# Cap_Sensor_8x8.net
KiCad netlist of a schematic drawn in Altium Designer
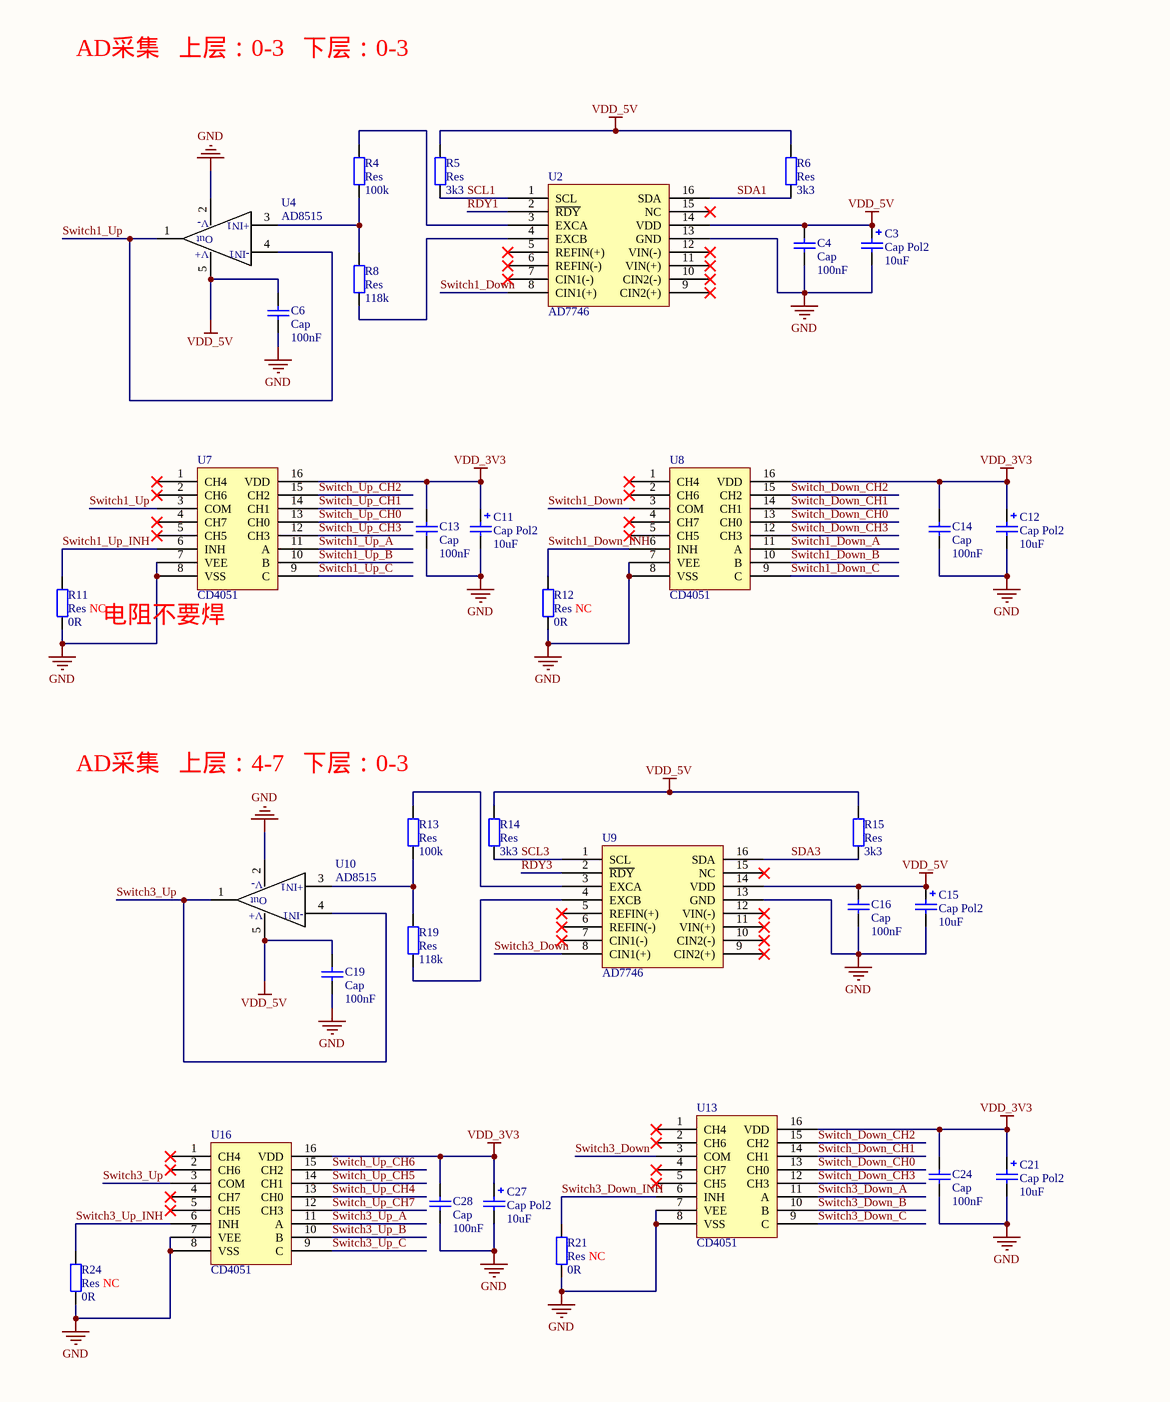
[diagram p0: Cap_Sensor_8x8.SchDoc, left]
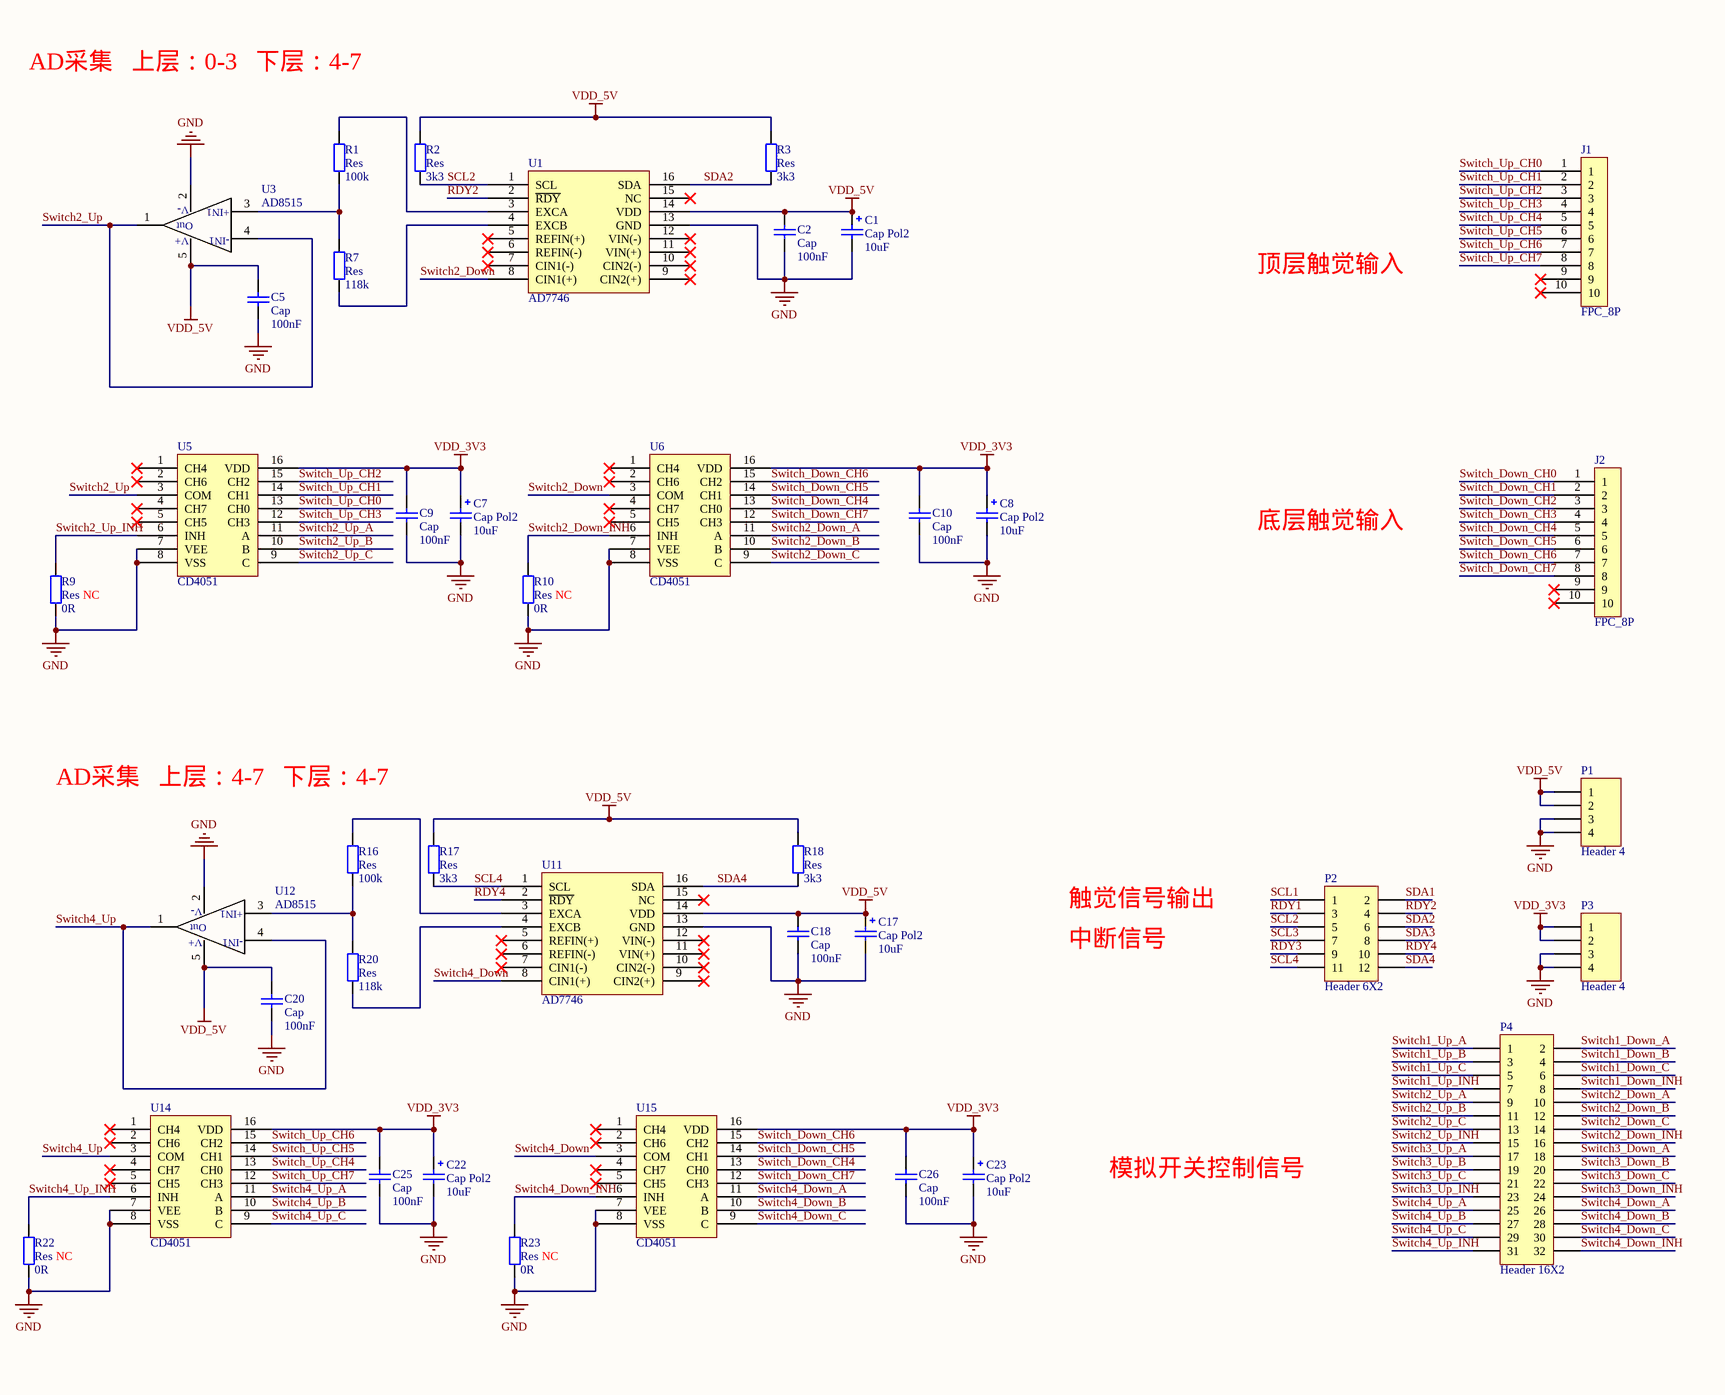
[diagram p1: Cap_Sensor_8x8.SchDoc, right]

(export (version "E")
  (design (tool "Eeschema 10.0.6"))
  (components
    (comp (ref "C1")
      (value "Cap Pol2")
      (footprint "Cap-TA")
      (description "Polarized Capacitor (Axial)")
      (fields (field (name "ALTIUM_VALUE") "10uF") (field (name "PUBLISHER") "Altium Limited"))
      (libsource (lib "YD-LibrarySCH") (part "Cap Pol2"))
    )
    (comp (ref "C2")
      (value "Cap")
      (footprint "0805C")
      (description "Capacitor")
      (fields (field (name "ALTIUM_VALUE") "100nF") (field (name "PUBLISHER") "Altium Limited"))
      (libsource (lib "YD-LibrarySCH") (part "Cap"))
    )
    (comp (ref "C3")
      (value "Cap Pol2")
      (footprint "Cap-TA")
      (description "Polarized Capacitor (Axial)")
      (fields (field (name "ALTIUM_VALUE") "10uF") (field (name "PUBLISHER") "Altium Limited"))
      (libsource (lib "YD-LibrarySCH") (part "Cap Pol2"))
    )
    (comp (ref "C4")
      (value "Cap")
      (footprint "0805C")
      (description "Capacitor")
      (fields (field (name "ALTIUM_VALUE") "100nF") (field (name "PUBLISHER") "Altium Limited"))
      (libsource (lib "YD-LibrarySCH") (part "Cap"))
    )
    (comp (ref "C5")
      (value "Cap")
      (footprint "0805C")
      (description "Capacitor")
      (fields (field (name "ALTIUM_VALUE") "100nF") (field (name "PUBLISHER") "Altium Limited"))
      (libsource (lib "YD-LibrarySCH") (part "Cap"))
    )
    (comp (ref "C6")
      (value "Cap")
      (footprint "0805C")
      (description "Capacitor")
      (fields (field (name "ALTIUM_VALUE") "100nF") (field (name "PUBLISHER") "Altium Limited"))
      (libsource (lib "YD-LibrarySCH") (part "Cap"))
    )
    (comp (ref "C7")
      (value "Cap Pol2")
      (footprint "Cap-TA")
      (description "Polarized Capacitor (Axial)")
      (fields (field (name "ALTIUM_VALUE") "10uF") (field (name "PUBLISHER") "Altium Limited"))
      (libsource (lib "YD-LibrarySCH") (part "Cap Pol2"))
    )
    (comp (ref "C8")
      (value "Cap Pol2")
      (footprint "Cap-TA")
      (description "Polarized Capacitor (Axial)")
      (fields (field (name "ALTIUM_VALUE") "10uF") (field (name "PUBLISHER") "Altium Limited"))
      (libsource (lib "YD-LibrarySCH") (part "Cap Pol2"))
    )
    (comp (ref "C9")
      (value "Cap")
      (footprint "0805C")
      (description "Capacitor")
      (fields (field (name "ALTIUM_VALUE") "100nF") (field (name "PUBLISHER") "Altium Limited"))
      (libsource (lib "YD-LibrarySCH") (part "Cap"))
    )
    (comp (ref "C10")
      (value "Cap")
      (footprint "0805C")
      (description "Capacitor")
      (fields (field (name "ALTIUM_VALUE") "100nF") (field (name "PUBLISHER") "Altium Limited"))
      (libsource (lib "YD-LibrarySCH") (part "Cap"))
    )
    (comp (ref "C11")
      (value "Cap Pol2")
      (footprint "Cap-TA")
      (description "Polarized Capacitor (Axial)")
      (fields (field (name "ALTIUM_VALUE") "10uF") (field (name "PUBLISHER") "Altium Limited"))
      (libsource (lib "YD-LibrarySCH") (part "Cap Pol2"))
    )
    (comp (ref "C12")
      (value "Cap Pol2")
      (footprint "Cap-TA")
      (description "Polarized Capacitor (Axial)")
      (fields (field (name "ALTIUM_VALUE") "10uF") (field (name "PUBLISHER") "Altium Limited"))
      (libsource (lib "YD-LibrarySCH") (part "Cap Pol2"))
    )
    (comp (ref "C13")
      (value "Cap")
      (footprint "0805C")
      (description "Capacitor")
      (fields (field (name "ALTIUM_VALUE") "100nF") (field (name "PUBLISHER") "Altium Limited"))
      (libsource (lib "YD-LibrarySCH") (part "Cap"))
    )
    (comp (ref "C14")
      (value "Cap")
      (footprint "0805C")
      (description "Capacitor")
      (fields (field (name "ALTIUM_VALUE") "100nF") (field (name "PUBLISHER") "Altium Limited"))
      (libsource (lib "YD-LibrarySCH") (part "Cap"))
    )
    (comp (ref "C15")
      (value "Cap Pol2")
      (footprint "Cap-TA")
      (description "Polarized Capacitor (Axial)")
      (fields (field (name "ALTIUM_VALUE") "10uF") (field (name "PUBLISHER") "Altium Limited"))
      (libsource (lib "YD-LibrarySCH") (part "Cap Pol2"))
    )
    (comp (ref "C16")
      (value "Cap")
      (footprint "0805C")
      (description "Capacitor")
      (fields (field (name "ALTIUM_VALUE") "100nF") (field (name "PUBLISHER") "Altium Limited"))
      (libsource (lib "YD-LibrarySCH") (part "Cap"))
    )
    (comp (ref "C17")
      (value "Cap Pol2")
      (footprint "Cap-TA")
      (description "Polarized Capacitor (Axial)")
      (fields (field (name "ALTIUM_VALUE") "10uF") (field (name "PUBLISHER") "Altium Limited"))
      (libsource (lib "YD-LibrarySCH") (part "Cap Pol2"))
    )
    (comp (ref "C18")
      (value "Cap")
      (footprint "0805C")
      (description "Capacitor")
      (fields (field (name "ALTIUM_VALUE") "100nF") (field (name "PUBLISHER") "Altium Limited"))
      (libsource (lib "YD-LibrarySCH") (part "Cap"))
    )
    (comp (ref "C19")
      (value "Cap")
      (footprint "0805C")
      (description "Capacitor")
      (fields (field (name "ALTIUM_VALUE") "100nF") (field (name "PUBLISHER") "Altium Limited"))
      (libsource (lib "YD-LibrarySCH") (part "Cap"))
    )
    (comp (ref "C20")
      (value "Cap")
      (footprint "0805C")
      (description "Capacitor")
      (fields (field (name "ALTIUM_VALUE") "100nF") (field (name "PUBLISHER") "Altium Limited"))
      (libsource (lib "YD-LibrarySCH") (part "Cap"))
    )
    (comp (ref "C21")
      (value "Cap Pol2")
      (footprint "Cap-TA")
      (description "Polarized Capacitor (Axial)")
      (fields (field (name "ALTIUM_VALUE") "10uF") (field (name "PUBLISHER") "Altium Limited"))
      (libsource (lib "YD-LibrarySCH") (part "Cap Pol2"))
    )
    (comp (ref "C22")
      (value "Cap Pol2")
      (footprint "Cap-TA")
      (description "Polarized Capacitor (Axial)")
      (fields (field (name "ALTIUM_VALUE") "10uF") (field (name "PUBLISHER") "Altium Limited"))
      (libsource (lib "YD-LibrarySCH") (part "Cap Pol2"))
    )
    (comp (ref "C23")
      (value "Cap Pol2")
      (footprint "Cap-TA")
      (description "Polarized Capacitor (Axial)")
      (fields (field (name "ALTIUM_VALUE") "10uF") (field (name "PUBLISHER") "Altium Limited"))
      (libsource (lib "YD-LibrarySCH") (part "Cap Pol2"))
    )
    (comp (ref "C24")
      (value "Cap")
      (footprint "0805C")
      (description "Capacitor")
      (fields (field (name "ALTIUM_VALUE") "100nF") (field (name "PUBLISHER") "Altium Limited"))
      (libsource (lib "YD-LibrarySCH") (part "Cap"))
    )
    (comp (ref "C25")
      (value "Cap")
      (footprint "0805C")
      (description "Capacitor")
      (fields (field (name "ALTIUM_VALUE") "100nF") (field (name "PUBLISHER") "Altium Limited"))
      (libsource (lib "YD-LibrarySCH") (part "Cap"))
    )
    (comp (ref "C26")
      (value "Cap")
      (footprint "0805C")
      (description "Capacitor")
      (fields (field (name "ALTIUM_VALUE") "100nF") (field (name "PUBLISHER") "Altium Limited"))
      (libsource (lib "YD-LibrarySCH") (part "Cap"))
    )
    (comp (ref "C27")
      (value "Cap Pol2")
      (footprint "Cap-TA")
      (description "Polarized Capacitor (Axial)")
      (fields (field (name "ALTIUM_VALUE") "10uF") (field (name "PUBLISHER") "Altium Limited"))
      (libsource (lib "YD-LibrarySCH") (part "Cap Pol2"))
    )
    (comp (ref "C28")
      (value "Cap")
      (footprint "0805C")
      (description "Capacitor")
      (fields (field (name "ALTIUM_VALUE") "100nF") (field (name "PUBLISHER") "Altium Limited"))
      (libsource (lib "YD-LibrarySCH") (part "Cap"))
    )
    (comp (ref "J1")
      (value "FPC_8P")
      (footprint "FPC8-0.5")
      (libsource (lib "YD-LibrarySCH") (part "FPC_8P"))
    )
    (comp (ref "J2")
      (value "FPC_8P")
      (footprint "FPC8-0.5")
      (libsource (lib "YD-LibrarySCH") (part "FPC_8P"))
    )
    (comp (ref "P1")
      (value "Header 4")
      (footprint "HDR1X4")
      (description "Header, 4-Pin")
      (fields (field (name "PUBLISHER") "Altium Limited"))
      (libsource (lib "YD-LibrarySCH") (part "Header 4"))
    )
    (comp (ref "P2")
      (value "Header 6X2")
      (footprint "HDR2X6")
      (description "Header, 6-Pin, Dual row")
      (fields (field (name "PUBLISHER") "Altium Limited"))
      (libsource (lib "YD-LibrarySCH") (part "Header 6X2"))
    )
    (comp (ref "P3")
      (value "Header 4")
      (footprint "HDR1X4")
      (description "Header, 4-Pin")
      (fields (field (name "PUBLISHER") "Altium Limited"))
      (libsource (lib "YD-LibrarySCH") (part "Header 4"))
    )
    (comp (ref "P4")
      (value "Header 16X2")
      (footprint "HDR2X16")
      (description "Header, 16-Pin, Dual row")
      (fields (field (name "PUBLISHER") "Altium Limited"))
      (libsource (lib "YD-LibrarySCH") (part "Header 16X2"))
    )
    (comp (ref "R1")
      (value "Res")
      (footprint "0805R")
      (description "Resistor")
      (fields (field (name "ALTIUM_VALUE") "100k") (field (name "PUBLISHER") "Altium Limited"))
      (libsource (lib "") (part "Res_1"))
    )
    (comp (ref "R2")
      (value "Res")
      (footprint "0805R")
      (description "Resistor")
      (fields (field (name "ALTIUM_VALUE") "3k3") (field (name "PUBLISHER") "Altium Limited"))
      (libsource (lib "YD-LibrarySCH") (part "Res"))
    )
    (comp (ref "R3")
      (value "Res")
      (footprint "0805R")
      (description "Resistor")
      (fields (field (name "ALTIUM_VALUE") "3k3") (field (name "PUBLISHER") "Altium Limited"))
      (libsource (lib "YD-LibrarySCH") (part "Res"))
    )
    (comp (ref "R4")
      (value "Res")
      (footprint "0805R")
      (description "Resistor")
      (fields (field (name "ALTIUM_VALUE") "100k") (field (name "PUBLISHER") "Altium Limited"))
      (libsource (lib "") (part "Res_1"))
    )
    (comp (ref "R5")
      (value "Res")
      (footprint "0805R")
      (description "Resistor")
      (fields (field (name "ALTIUM_VALUE") "3k3") (field (name "PUBLISHER") "Altium Limited"))
      (libsource (lib "YD-LibrarySCH") (part "Res"))
    )
    (comp (ref "R6")
      (value "Res")
      (footprint "0805R")
      (description "Resistor")
      (fields (field (name "ALTIUM_VALUE") "3k3") (field (name "PUBLISHER") "Altium Limited"))
      (libsource (lib "YD-LibrarySCH") (part "Res"))
    )
    (comp (ref "R7")
      (value "Res")
      (footprint "0805R")
      (description "Resistor")
      (fields (field (name "ALTIUM_VALUE") "118k") (field (name "PUBLISHER") "Altium Limited"))
      (libsource (lib "") (part "Res_1"))
    )
    (comp (ref "R8")
      (value "Res")
      (footprint "0805R")
      (description "Resistor")
      (fields (field (name "ALTIUM_VALUE") "118k") (field (name "PUBLISHER") "Altium Limited"))
      (libsource (lib "") (part "Res_1"))
    )
    (comp (ref "R9")
      (value "Res")
      (footprint "0805R")
      (description "Resistor")
      (fields (field (name "ALTIUM_VALUE") "0R") (field (name "PUBLISHER") "Altium Limited"))
      (libsource (lib "YD-LibrarySCH") (part "Res"))
    )
    (comp (ref "R10")
      (value "Res")
      (footprint "0603R")
      (description "Resistor")
      (fields (field (name "ALTIUM_VALUE") "0R") (field (name "PUBLISHER") "Altium Limited"))
      (libsource (lib "YD-LibrarySCH") (part "Res"))
    )
    (comp (ref "R11")
      (value "Res")
      (footprint "0805R")
      (description "Resistor")
      (fields (field (name "ALTIUM_VALUE") "0R") (field (name "PUBLISHER") "Altium Limited"))
      (libsource (lib "YD-LibrarySCH") (part "Res"))
    )
    (comp (ref "R12")
      (value "Res")
      (footprint "0603R")
      (description "Resistor")
      (fields (field (name "ALTIUM_VALUE") "0R") (field (name "PUBLISHER") "Altium Limited"))
      (libsource (lib "YD-LibrarySCH") (part "Res"))
    )
    (comp (ref "R13")
      (value "Res")
      (footprint "0805R")
      (description "Resistor")
      (fields (field (name "ALTIUM_VALUE") "100k") (field (name "PUBLISHER") "Altium Limited"))
      (libsource (lib "") (part "Res_1"))
    )
    (comp (ref "R14")
      (value "Res")
      (footprint "0805R")
      (description "Resistor")
      (fields (field (name "ALTIUM_VALUE") "3k3") (field (name "PUBLISHER") "Altium Limited"))
      (libsource (lib "YD-LibrarySCH") (part "Res"))
    )
    (comp (ref "R15")
      (value "Res")
      (footprint "0805R")
      (description "Resistor")
      (fields (field (name "ALTIUM_VALUE") "3k3") (field (name "PUBLISHER") "Altium Limited"))
      (libsource (lib "YD-LibrarySCH") (part "Res"))
    )
    (comp (ref "R16")
      (value "Res")
      (footprint "0805R")
      (description "Resistor")
      (fields (field (name "ALTIUM_VALUE") "100k") (field (name "PUBLISHER") "Altium Limited"))
      (libsource (lib "") (part "Res_1"))
    )
    (comp (ref "R17")
      (value "Res")
      (footprint "0805R")
      (description "Resistor")
      (fields (field (name "ALTIUM_VALUE") "3k3") (field (name "PUBLISHER") "Altium Limited"))
      (libsource (lib "YD-LibrarySCH") (part "Res"))
    )
    (comp (ref "R18")
      (value "Res")
      (footprint "0805R")
      (description "Resistor")
      (fields (field (name "ALTIUM_VALUE") "3k3") (field (name "PUBLISHER") "Altium Limited"))
      (libsource (lib "YD-LibrarySCH") (part "Res"))
    )
    (comp (ref "R19")
      (value "Res")
      (footprint "0805R")
      (description "Resistor")
      (fields (field (name "ALTIUM_VALUE") "118k") (field (name "PUBLISHER") "Altium Limited"))
      (libsource (lib "") (part "Res_1"))
    )
    (comp (ref "R20")
      (value "Res")
      (footprint "0805R")
      (description "Resistor")
      (fields (field (name "ALTIUM_VALUE") "118k") (field (name "PUBLISHER") "Altium Limited"))
      (libsource (lib "") (part "Res_1"))
    )
    (comp (ref "R21")
      (value "Res")
      (footprint "0603R")
      (description "Resistor")
      (fields (field (name "ALTIUM_VALUE") "0R") (field (name "PUBLISHER") "Altium Limited"))
      (libsource (lib "YD-LibrarySCH") (part "Res"))
    )
    (comp (ref "R22")
      (value "Res")
      (footprint "0805R")
      (description "Resistor")
      (fields (field (name "ALTIUM_VALUE") "0R") (field (name "PUBLISHER") "Altium Limited"))
      (libsource (lib "YD-LibrarySCH") (part "Res"))
    )
    (comp (ref "R23")
      (value "Res")
      (footprint "0603R")
      (description "Resistor")
      (fields (field (name "ALTIUM_VALUE") "0R") (field (name "PUBLISHER") "Altium Limited"))
      (libsource (lib "YD-LibrarySCH") (part "Res"))
    )
    (comp (ref "R24")
      (value "Res")
      (footprint "0805R")
      (description "Resistor")
      (fields (field (name "ALTIUM_VALUE") "0R") (field (name "PUBLISHER") "Altium Limited"))
      (libsource (lib "YD-LibrarySCH") (part "Res"))
    )
    (comp (ref "U1") (value "AD7746") (footprint "TSSOP16") (libsource (lib "YD-LibrarySCH") (part "AD7746")))
    (comp (ref "U2") (value "AD7746") (footprint "TSSOP16") (libsource (lib "YD-LibrarySCH") (part "AD7746")))
    (comp (ref "U3") (value "AD8515") (footprint "sot23-5") (libsource (lib "YD-LibrarySCH") (part "AD8515")))
    (comp (ref "U4") (value "AD8515") (footprint "sot23-5") (libsource (lib "YD-LibrarySCH") (part "AD8515")))
    (comp (ref "U5") (value "CD4051") (footprint "SO16") (libsource (lib "YD-LibrarySCH") (part "CD4051")))
    (comp (ref "U6") (value "CD4051") (footprint "SO16") (libsource (lib "YD-LibrarySCH") (part "CD4051")))
    (comp (ref "U7") (value "CD4051") (footprint "SO16") (libsource (lib "YD-LibrarySCH") (part "CD4051")))
    (comp (ref "U8") (value "CD4051") (footprint "SO16") (libsource (lib "YD-LibrarySCH") (part "CD4051")))
    (comp (ref "U9") (value "AD7746") (footprint "TSSOP16") (libsource (lib "YD-LibrarySCH") (part "AD7746")))
    (comp (ref "U10")
      (value "AD8515")
      (footprint "sot23-5")
      (libsource (lib "YD-LibrarySCH") (part "AD8515"))
    )
    (comp (ref "U11")
      (value "AD7746")
      (footprint "TSSOP16")
      (libsource (lib "YD-LibrarySCH") (part "AD7746"))
    )
    (comp (ref "U12")
      (value "AD8515")
      (footprint "sot23-5")
      (libsource (lib "YD-LibrarySCH") (part "AD8515"))
    )
    (comp (ref "U13") (value "CD4051") (footprint "SO16") (libsource (lib "YD-LibrarySCH") (part "CD4051")))
    (comp (ref "U14") (value "CD4051") (footprint "SO16") (libsource (lib "YD-LibrarySCH") (part "CD4051")))
    (comp (ref "U15") (value "CD4051") (footprint "SO16") (libsource (lib "YD-LibrarySCH") (part "CD4051")))
    (comp (ref "U16") (value "CD4051") (footprint "SO16") (libsource (lib "YD-LibrarySCH") (part "CD4051")))
  )
  (nets
    (net (code "1") (name "/RDY1") (class "Default")
      (node (ref "P2") (pin "3") (pinfunction "3_3") (pintype "passive"))
      (node (ref "U2") (pin "2") (pinfunction "~{RDY}_2") (pintype "passive"))
    )
    (net (code "2") (name "/RDY2") (class "Default")
      (node (ref "P2") (pin "4") (pinfunction "4_4") (pintype "passive"))
      (node (ref "U1") (pin "2") (pinfunction "~{RDY}_2") (pintype "passive"))
    )
    (net (code "3") (name "/RDY3") (class "Default")
      (node (ref "P2") (pin "9") (pinfunction "9_9") (pintype "passive"))
      (node (ref "U9") (pin "2") (pinfunction "~{RDY}_2") (pintype "passive"))
    )
    (net (code "4") (name "/RDY4") (class "Default")
      (node (ref "P2") (pin "10") (pinfunction "10_10") (pintype "passive"))
      (node (ref "U11") (pin "2") (pinfunction "~{RDY}_2") (pintype "passive"))
    )
    (net (code "5") (name "/SCL1") (class "Default")
      (node (ref "P2") (pin "1") (pinfunction "1_1") (pintype "passive"))
      (node (ref "R5") (pin "1") (pinfunction "1_1") (pintype "passive"))
      (node (ref "U2") (pin "1") (pinfunction "SCL_1") (pintype "passive"))
    )
    (net (code "6") (name "/SCL2") (class "Default")
      (node (ref "P2") (pin "5") (pinfunction "5_5") (pintype "passive"))
      (node (ref "R2") (pin "1") (pinfunction "1_1") (pintype "passive"))
      (node (ref "U1") (pin "1") (pinfunction "SCL_1") (pintype "passive"))
    )
    (net (code "7") (name "/SCL3") (class "Default")
      (node (ref "P2") (pin "7") (pinfunction "7_7") (pintype "passive"))
      (node (ref "R14") (pin "1") (pinfunction "1_1") (pintype "passive"))
      (node (ref "U9") (pin "1") (pinfunction "SCL_1") (pintype "passive"))
    )
    (net (code "8") (name "/SCL4") (class "Default")
      (node (ref "P2") (pin "11") (pinfunction "11_11") (pintype "passive"))
      (node (ref "R17") (pin "1") (pinfunction "1_1") (pintype "passive"))
      (node (ref "U11") (pin "1") (pinfunction "SCL_1") (pintype "passive"))
    )
    (net (code "9") (name "/SDA1") (class "Default")
      (node (ref "P2") (pin "2") (pinfunction "2_2") (pintype "passive"))
      (node (ref "R6") (pin "1") (pinfunction "1_1") (pintype "passive"))
      (node (ref "U2") (pin "16") (pinfunction "SDA_16") (pintype "passive"))
    )
    (net (code "10") (name "/SDA2") (class "Default")
      (node (ref "P2") (pin "6") (pinfunction "6_6") (pintype "passive"))
      (node (ref "R3") (pin "1") (pinfunction "1_1") (pintype "passive"))
      (node (ref "U1") (pin "16") (pinfunction "SDA_16") (pintype "passive"))
    )
    (net (code "11") (name "/SDA3") (class "Default")
      (node (ref "P2") (pin "8") (pinfunction "8_8") (pintype "passive"))
      (node (ref "R15") (pin "1") (pinfunction "1_1") (pintype "passive"))
      (node (ref "U9") (pin "16") (pinfunction "SDA_16") (pintype "passive"))
    )
    (net (code "12") (name "/SDA4") (class "Default")
      (node (ref "P2") (pin "12") (pinfunction "12_12") (pintype "passive"))
      (node (ref "R18") (pin "1") (pinfunction "1_1") (pintype "passive"))
      (node (ref "U11") (pin "16") (pinfunction "SDA_16") (pintype "passive"))
    )
    (net (code "13") (name "/Switch1_Down") (class "Default")
      (node (ref "U2") (pin "8") (pinfunction "CIN1(+)_8") (pintype "passive"))
      (node (ref "U8") (pin "3") (pinfunction "COM_3") (pintype "passive"))
    )
    (net (code "14") (name "/Switch1_Down_A") (class "Default")
      (node (ref "P4") (pin "2") (pinfunction "2_2") (pintype "passive"))
      (node (ref "U8") (pin "11") (pinfunction "A_11") (pintype "passive"))
    )
    (net (code "15") (name "/Switch1_Down_B") (class "Default")
      (node (ref "P4") (pin "4") (pinfunction "4_4") (pintype "passive"))
      (node (ref "U8") (pin "10") (pinfunction "B_10") (pintype "passive"))
    )
    (net (code "16") (name "/Switch1_Down_C") (class "Default")
      (node (ref "P4") (pin "6") (pinfunction "6_6") (pintype "passive"))
      (node (ref "U8") (pin "9") (pinfunction "C_9") (pintype "passive"))
    )
    (net (code "17") (name "/Switch1_Down_INH") (class "Default")
      (node (ref "P4") (pin "8") (pinfunction "8_8") (pintype "passive"))
      (node (ref "R12") (pin "2") (pinfunction "2_2") (pintype "passive"))
      (node (ref "U8") (pin "6") (pinfunction "INH_6") (pintype "passive"))
    )
    (net (code "18") (name "/Switch1_Up") (class "Default")
      (node (ref "U4") (pin "1") (pinfunction "Out1_1") (pintype "passive"))
      (node (ref "U4") (pin "4") (pinfunction "-IN_4") (pintype "passive"))
      (node (ref "U7") (pin "3") (pinfunction "COM_3") (pintype "passive"))
    )
    (net (code "19") (name "/Switch1_Up_A") (class "Default")
      (node (ref "P4") (pin "1") (pinfunction "1_1") (pintype "passive"))
      (node (ref "U7") (pin "11") (pinfunction "A_11") (pintype "passive"))
    )
    (net (code "20") (name "/Switch1_Up_B") (class "Default")
      (node (ref "P4") (pin "3") (pinfunction "3_3") (pintype "passive"))
      (node (ref "U7") (pin "10") (pinfunction "B_10") (pintype "passive"))
    )
    (net (code "21") (name "/Switch1_Up_C") (class "Default")
      (node (ref "P4") (pin "5") (pinfunction "5_5") (pintype "passive"))
      (node (ref "U7") (pin "9") (pinfunction "C_9") (pintype "passive"))
    )
    (net (code "22") (name "/Switch1_Up_INH") (class "Default")
      (node (ref "P4") (pin "7") (pinfunction "7_7") (pintype "passive"))
      (node (ref "R11") (pin "2") (pinfunction "2_2") (pintype "passive"))
      (node (ref "U7") (pin "6") (pinfunction "INH_6") (pintype "passive"))
    )
    (net (code "23") (name "/Switch2_Down") (class "Default")
      (node (ref "U1") (pin "8") (pinfunction "CIN1(+)_8") (pintype "passive"))
      (node (ref "U6") (pin "3") (pinfunction "COM_3") (pintype "passive"))
    )
    (net (code "24") (name "/Switch2_Down_A") (class "Default")
      (node (ref "P4") (pin "10") (pinfunction "10_10") (pintype "passive"))
      (node (ref "U6") (pin "11") (pinfunction "A_11") (pintype "passive"))
    )
    (net (code "25") (name "/Switch2_Down_B") (class "Default")
      (node (ref "P4") (pin "12") (pinfunction "12_12") (pintype "passive"))
      (node (ref "U6") (pin "10") (pinfunction "B_10") (pintype "passive"))
    )
    (net (code "26") (name "/Switch2_Down_C") (class "Default")
      (node (ref "P4") (pin "14") (pinfunction "14_14") (pintype "passive"))
      (node (ref "U6") (pin "9") (pinfunction "C_9") (pintype "passive"))
    )
    (net (code "27") (name "/Switch2_Down_INH") (class "Default")
      (node (ref "P4") (pin "16") (pinfunction "16_16") (pintype "passive"))
      (node (ref "R10") (pin "2") (pinfunction "2_2") (pintype "passive"))
      (node (ref "U6") (pin "6") (pinfunction "INH_6") (pintype "passive"))
    )
    (net (code "28") (name "/Switch2_Up") (class "Default")
      (node (ref "U3") (pin "1") (pinfunction "Out1_1") (pintype "passive"))
      (node (ref "U3") (pin "4") (pinfunction "-IN_4") (pintype "passive"))
      (node (ref "U5") (pin "3") (pinfunction "COM_3") (pintype "passive"))
    )
    (net (code "29") (name "/Switch2_Up_A") (class "Default")
      (node (ref "P4") (pin "9") (pinfunction "9_9") (pintype "passive"))
      (node (ref "U5") (pin "11") (pinfunction "A_11") (pintype "passive"))
    )
    (net (code "30") (name "/Switch2_Up_B") (class "Default")
      (node (ref "P4") (pin "11") (pinfunction "11_11") (pintype "passive"))
      (node (ref "U5") (pin "10") (pinfunction "B_10") (pintype "passive"))
    )
    (net (code "31") (name "/Switch2_Up_C") (class "Default")
      (node (ref "P4") (pin "13") (pinfunction "13_13") (pintype "passive"))
      (node (ref "U5") (pin "9") (pinfunction "C_9") (pintype "passive"))
    )
    (net (code "32") (name "/Switch2_Up_INH") (class "Default")
      (node (ref "P4") (pin "15") (pinfunction "15_15") (pintype "passive"))
      (node (ref "R9") (pin "2") (pinfunction "2_2") (pintype "passive"))
      (node (ref "U5") (pin "6") (pinfunction "INH_6") (pintype "passive"))
    )
    (net (code "33") (name "/Switch3_Down") (class "Default")
      (node (ref "U13") (pin "3") (pinfunction "COM_3") (pintype "passive"))
      (node (ref "U9") (pin "8") (pinfunction "CIN1(+)_8") (pintype "passive"))
    )
    (net (code "34") (name "/Switch3_Down_A") (class "Default")
      (node (ref "P4") (pin "18") (pinfunction "18_18") (pintype "passive"))
      (node (ref "U13") (pin "11") (pinfunction "A_11") (pintype "passive"))
    )
    (net (code "35") (name "/Switch3_Down_B") (class "Default")
      (node (ref "P4") (pin "20") (pinfunction "20_20") (pintype "passive"))
      (node (ref "U13") (pin "10") (pinfunction "B_10") (pintype "passive"))
    )
    (net (code "36") (name "/Switch3_Down_C") (class "Default")
      (node (ref "P4") (pin "22") (pinfunction "22_22") (pintype "passive"))
      (node (ref "U13") (pin "9") (pinfunction "C_9") (pintype "passive"))
    )
    (net (code "37") (name "/Switch3_Down_INH") (class "Default")
      (node (ref "P4") (pin "24") (pinfunction "24_24") (pintype "passive"))
      (node (ref "R21") (pin "2") (pinfunction "2_2") (pintype "passive"))
      (node (ref "U13") (pin "6") (pinfunction "INH_6") (pintype "passive"))
    )
    (net (code "38") (name "/Switch3_Up") (class "Default")
      (node (ref "U10") (pin "1") (pinfunction "Out1_1") (pintype "passive"))
      (node (ref "U10") (pin "4") (pinfunction "-IN_4") (pintype "passive"))
      (node (ref "U16") (pin "3") (pinfunction "COM_3") (pintype "passive"))
    )
    (net (code "39") (name "/Switch3_Up_A") (class "Default")
      (node (ref "P4") (pin "17") (pinfunction "17_17") (pintype "passive"))
      (node (ref "U16") (pin "11") (pinfunction "A_11") (pintype "passive"))
    )
    (net (code "40") (name "/Switch3_Up_B") (class "Default")
      (node (ref "P4") (pin "19") (pinfunction "19_19") (pintype "passive"))
      (node (ref "U16") (pin "10") (pinfunction "B_10") (pintype "passive"))
    )
    (net (code "41") (name "/Switch3_Up_C") (class "Default")
      (node (ref "P4") (pin "21") (pinfunction "21_21") (pintype "passive"))
      (node (ref "U16") (pin "9") (pinfunction "C_9") (pintype "passive"))
    )
    (net (code "42") (name "/Switch3_Up_INH") (class "Default")
      (node (ref "P4") (pin "23") (pinfunction "23_23") (pintype "passive"))
      (node (ref "R24") (pin "2") (pinfunction "2_2") (pintype "passive"))
      (node (ref "U16") (pin "6") (pinfunction "INH_6") (pintype "passive"))
    )
    (net (code "43") (name "/Switch4_Down") (class "Default")
      (node (ref "U11") (pin "8") (pinfunction "CIN1(+)_8") (pintype "passive"))
      (node (ref "U15") (pin "3") (pinfunction "COM_3") (pintype "passive"))
    )
    (net (code "44") (name "/Switch4_Down_A") (class "Default")
      (node (ref "P4") (pin "26") (pinfunction "26_26") (pintype "passive"))
      (node (ref "U15") (pin "11") (pinfunction "A_11") (pintype "passive"))
    )
    (net (code "45") (name "/Switch4_Down_B") (class "Default")
      (node (ref "P4") (pin "28") (pinfunction "28_28") (pintype "passive"))
      (node (ref "U15") (pin "10") (pinfunction "B_10") (pintype "passive"))
    )
    (net (code "46") (name "/Switch4_Down_C") (class "Default")
      (node (ref "P4") (pin "30") (pinfunction "30_30") (pintype "passive"))
      (node (ref "U15") (pin "9") (pinfunction "C_9") (pintype "passive"))
    )
    (net (code "47") (name "/Switch4_Down_INH") (class "Default")
      (node (ref "P4") (pin "32") (pinfunction "32_32") (pintype "passive"))
      (node (ref "R23") (pin "2") (pinfunction "2_2") (pintype "passive"))
      (node (ref "U15") (pin "6") (pinfunction "INH_6") (pintype "passive"))
    )
    (net (code "48") (name "/Switch4_Up") (class "Default")
      (node (ref "U12") (pin "1") (pinfunction "Out1_1") (pintype "passive"))
      (node (ref "U12") (pin "4") (pinfunction "-IN_4") (pintype "passive"))
      (node (ref "U14") (pin "3") (pinfunction "COM_3") (pintype "passive"))
    )
    (net (code "49") (name "/Switch4_Up_A") (class "Default")
      (node (ref "P4") (pin "25") (pinfunction "25_25") (pintype "passive"))
      (node (ref "U14") (pin "11") (pinfunction "A_11") (pintype "passive"))
    )
    (net (code "50") (name "/Switch4_Up_B") (class "Default")
      (node (ref "P4") (pin "27") (pinfunction "27_27") (pintype "passive"))
      (node (ref "U14") (pin "10") (pinfunction "B_10") (pintype "passive"))
    )
    (net (code "51") (name "/Switch4_Up_C") (class "Default")
      (node (ref "P4") (pin "29") (pinfunction "29_29") (pintype "passive"))
      (node (ref "U14") (pin "9") (pinfunction "C_9") (pintype "passive"))
    )
    (net (code "52") (name "/Switch4_Up_INH") (class "Default")
      (node (ref "P4") (pin "31") (pinfunction "31_31") (pintype "passive"))
      (node (ref "R22") (pin "2") (pinfunction "2_2") (pintype "passive"))
      (node (ref "U14") (pin "6") (pinfunction "INH_6") (pintype "passive"))
    )
    (net (code "53") (name "/Switch_Down_CH0") (class "Default")
      (node (ref "J2") (pin "1") (pinfunction "1_1") (pintype "passive"))
      (node (ref "U13") (pin "13") (pinfunction "CH0_13") (pintype "passive"))
      (node (ref "U8") (pin "13") (pinfunction "CH0_13") (pintype "passive"))
    )
    (net (code "54") (name "/Switch_Down_CH1") (class "Default")
      (node (ref "J2") (pin "2") (pinfunction "2_2") (pintype "passive"))
      (node (ref "U13") (pin "14") (pinfunction "CH1_14") (pintype "passive"))
      (node (ref "U8") (pin "14") (pinfunction "CH1_14") (pintype "passive"))
    )
    (net (code "55") (name "/Switch_Down_CH2") (class "Default")
      (node (ref "J2") (pin "3") (pinfunction "3_3") (pintype "passive"))
      (node (ref "U13") (pin "15") (pinfunction "CH2_15") (pintype "passive"))
      (node (ref "U8") (pin "15") (pinfunction "CH2_15") (pintype "passive"))
    )
    (net (code "56") (name "/Switch_Down_CH3") (class "Default")
      (node (ref "J2") (pin "4") (pinfunction "4_4") (pintype "passive"))
      (node (ref "U13") (pin "12") (pinfunction "CH3_12") (pintype "passive"))
      (node (ref "U8") (pin "12") (pinfunction "CH3_12") (pintype "passive"))
    )
    (net (code "57") (name "/Switch_Down_CH4") (class "Default")
      (node (ref "J2") (pin "5") (pinfunction "5_5") (pintype "passive"))
      (node (ref "U15") (pin "13") (pinfunction "CH0_13") (pintype "passive"))
      (node (ref "U6") (pin "13") (pinfunction "CH0_13") (pintype "passive"))
    )
    (net (code "58") (name "/Switch_Down_CH5") (class "Default")
      (node (ref "J2") (pin "6") (pinfunction "6_6") (pintype "passive"))
      (node (ref "U15") (pin "14") (pinfunction "CH1_14") (pintype "passive"))
      (node (ref "U6") (pin "14") (pinfunction "CH1_14") (pintype "passive"))
    )
    (net (code "59") (name "/Switch_Down_CH6") (class "Default")
      (node (ref "J2") (pin "7") (pinfunction "7_7") (pintype "passive"))
      (node (ref "U15") (pin "15") (pinfunction "CH2_15") (pintype "passive"))
      (node (ref "U6") (pin "15") (pinfunction "CH2_15") (pintype "passive"))
    )
    (net (code "60") (name "/Switch_Down_CH7") (class "Default")
      (node (ref "J2") (pin "8") (pinfunction "8_8") (pintype "passive"))
      (node (ref "U15") (pin "12") (pinfunction "CH3_12") (pintype "passive"))
      (node (ref "U6") (pin "12") (pinfunction "CH3_12") (pintype "passive"))
    )
    (net (code "61") (name "/Switch_Up_CH0") (class "Default")
      (node (ref "J1") (pin "1") (pinfunction "1_1") (pintype "passive"))
      (node (ref "U5") (pin "13") (pinfunction "CH0_13") (pintype "passive"))
      (node (ref "U7") (pin "13") (pinfunction "CH0_13") (pintype "passive"))
    )
    (net (code "62") (name "/Switch_Up_CH1") (class "Default")
      (node (ref "J1") (pin "2") (pinfunction "2_2") (pintype "passive"))
      (node (ref "U5") (pin "14") (pinfunction "CH1_14") (pintype "passive"))
      (node (ref "U7") (pin "14") (pinfunction "CH1_14") (pintype "passive"))
    )
    (net (code "63") (name "/Switch_Up_CH2") (class "Default")
      (node (ref "J1") (pin "3") (pinfunction "3_3") (pintype "passive"))
      (node (ref "U5") (pin "15") (pinfunction "CH2_15") (pintype "passive"))
      (node (ref "U7") (pin "15") (pinfunction "CH2_15") (pintype "passive"))
    )
    (net (code "64") (name "/Switch_Up_CH3") (class "Default")
      (node (ref "J1") (pin "4") (pinfunction "4_4") (pintype "passive"))
      (node (ref "U5") (pin "12") (pinfunction "CH3_12") (pintype "passive"))
      (node (ref "U7") (pin "12") (pinfunction "CH3_12") (pintype "passive"))
    )
    (net (code "65") (name "/Switch_Up_CH4") (class "Default")
      (node (ref "J1") (pin "5") (pinfunction "5_5") (pintype "passive"))
      (node (ref "U14") (pin "13") (pinfunction "CH0_13") (pintype "passive"))
      (node (ref "U16") (pin "13") (pinfunction "CH0_13") (pintype "passive"))
    )
    (net (code "66") (name "/Switch_Up_CH5") (class "Default")
      (node (ref "J1") (pin "6") (pinfunction "6_6") (pintype "passive"))
      (node (ref "U14") (pin "14") (pinfunction "CH1_14") (pintype "passive"))
      (node (ref "U16") (pin "14") (pinfunction "CH1_14") (pintype "passive"))
    )
    (net (code "67") (name "/Switch_Up_CH6") (class "Default")
      (node (ref "J1") (pin "7") (pinfunction "7_7") (pintype "passive"))
      (node (ref "U14") (pin "15") (pinfunction "CH2_15") (pintype "passive"))
      (node (ref "U16") (pin "15") (pinfunction "CH2_15") (pintype "passive"))
    )
    (net (code "68") (name "/Switch_Up_CH7") (class "Default")
      (node (ref "J1") (pin "8") (pinfunction "8_8") (pintype "passive"))
      (node (ref "U14") (pin "12") (pinfunction "CH3_12") (pintype "passive"))
      (node (ref "U16") (pin "12") (pinfunction "CH3_12") (pintype "passive"))
    )
    (net (code "69") (name "GND") (class "Default")
      (node (ref "C1") (pin "2") (pinfunction "2_2") (pintype "passive"))
      (node (ref "C10") (pin "1") (pinfunction "1_1") (pintype "passive"))
      (node (ref "C11") (pin "2") (pinfunction "2_2") (pintype "passive"))
      (node (ref "C12") (pin "2") (pinfunction "2_2") (pintype "passive"))
      (node (ref "C13") (pin "1") (pinfunction "1_1") (pintype "passive"))
      (node (ref "C14") (pin "1") (pinfunction "1_1") (pintype "passive"))
      (node (ref "C15") (pin "2") (pinfunction "2_2") (pintype "passive"))
      (node (ref "C16") (pin "1") (pinfunction "1_1") (pintype "passive"))
      (node (ref "C17") (pin "2") (pinfunction "2_2") (pintype "passive"))
      (node (ref "C18") (pin "1") (pinfunction "1_1") (pintype "passive"))
      (node (ref "C19") (pin "1") (pinfunction "1_1") (pintype "passive"))
      (node (ref "C2") (pin "1") (pinfunction "1_1") (pintype "passive"))
      (node (ref "C20") (pin "1") (pinfunction "1_1") (pintype "passive"))
      (node (ref "C21") (pin "2") (pinfunction "2_2") (pintype "passive"))
      (node (ref "C22") (pin "2") (pinfunction "2_2") (pintype "passive"))
      (node (ref "C23") (pin "2") (pinfunction "2_2") (pintype "passive"))
      (node (ref "C24") (pin "1") (pinfunction "1_1") (pintype "passive"))
      (node (ref "C25") (pin "1") (pinfunction "1_1") (pintype "passive"))
      (node (ref "C26") (pin "1") (pinfunction "1_1") (pintype "passive"))
      (node (ref "C27") (pin "2") (pinfunction "2_2") (pintype "passive"))
      (node (ref "C28") (pin "1") (pinfunction "1_1") (pintype "passive"))
      (node (ref "C3") (pin "2") (pinfunction "2_2") (pintype "passive"))
      (node (ref "C4") (pin "1") (pinfunction "1_1") (pintype "passive"))
      (node (ref "C5") (pin "1") (pinfunction "1_1") (pintype "passive"))
      (node (ref "C6") (pin "1") (pinfunction "1_1") (pintype "passive"))
      (node (ref "C7") (pin "2") (pinfunction "2_2") (pintype "passive"))
      (node (ref "C8") (pin "2") (pinfunction "2_2") (pintype "passive"))
      (node (ref "C9") (pin "1") (pinfunction "1_1") (pintype "passive"))
      (node (ref "P1") (pin "3") (pinfunction "3_3") (pintype "passive"))
      (node (ref "P1") (pin "4") (pinfunction "4_4") (pintype "passive"))
      (node (ref "P3") (pin "3") (pinfunction "3_3") (pintype "passive"))
      (node (ref "P3") (pin "4") (pinfunction "4_4") (pintype "passive"))
      (node (ref "R10") (pin "1") (pinfunction "1_1") (pintype "passive"))
      (node (ref "R11") (pin "1") (pinfunction "1_1") (pintype "passive"))
      (node (ref "R12") (pin "1") (pinfunction "1_1") (pintype "passive"))
      (node (ref "R21") (pin "1") (pinfunction "1_1") (pintype "passive"))
      (node (ref "R22") (pin "1") (pinfunction "1_1") (pintype "passive"))
      (node (ref "R23") (pin "1") (pinfunction "1_1") (pintype "passive"))
      (node (ref "R24") (pin "1") (pinfunction "1_1") (pintype "passive"))
      (node (ref "R9") (pin "1") (pinfunction "1_1") (pintype "passive"))
      (node (ref "U1") (pin "13") (pinfunction "GND_13") (pintype "passive"))
      (node (ref "U10") (pin "2") (pinfunction "V-_2") (pintype "passive"))
      (node (ref "U11") (pin "13") (pinfunction "GND_13") (pintype "passive"))
      (node (ref "U12") (pin "2") (pinfunction "V-_2") (pintype "passive"))
      (node (ref "U13") (pin "7") (pinfunction "VEE_7") (pintype "passive"))
      (node (ref "U13") (pin "8") (pinfunction "VSS_8") (pintype "passive"))
      (node (ref "U14") (pin "7") (pinfunction "VEE_7") (pintype "passive"))
      (node (ref "U14") (pin "8") (pinfunction "VSS_8") (pintype "passive"))
      (node (ref "U15") (pin "7") (pinfunction "VEE_7") (pintype "passive"))
      (node (ref "U15") (pin "8") (pinfunction "VSS_8") (pintype "passive"))
      (node (ref "U16") (pin "7") (pinfunction "VEE_7") (pintype "passive"))
      (node (ref "U16") (pin "8") (pinfunction "VSS_8") (pintype "passive"))
      (node (ref "U2") (pin "13") (pinfunction "GND_13") (pintype "passive"))
      (node (ref "U3") (pin "2") (pinfunction "V-_2") (pintype "passive"))
      (node (ref "U4") (pin "2") (pinfunction "V-_2") (pintype "passive"))
      (node (ref "U5") (pin "7") (pinfunction "VEE_7") (pintype "passive"))
      (node (ref "U5") (pin "8") (pinfunction "VSS_8") (pintype "passive"))
      (node (ref "U6") (pin "7") (pinfunction "VEE_7") (pintype "passive"))
      (node (ref "U6") (pin "8") (pinfunction "VSS_8") (pintype "passive"))
      (node (ref "U7") (pin "7") (pinfunction "VEE_7") (pintype "passive"))
      (node (ref "U7") (pin "8") (pinfunction "VSS_8") (pintype "passive"))
      (node (ref "U8") (pin "7") (pinfunction "VEE_7") (pintype "passive"))
      (node (ref "U8") (pin "8") (pinfunction "VSS_8") (pintype "passive"))
      (node (ref "U9") (pin "13") (pinfunction "GND_13") (pintype "passive"))
    )
    (net (code "70") (name "Net-(U1-EXCA)") (class "Default")
      (node (ref "R1") (pin "1") (pinfunction "1_1") (pintype "passive"))
      (node (ref "U1") (pin "3") (pinfunction "EXCA_3") (pintype "passive"))
    )
    (net (code "71") (name "Net-(U1-EXCB)") (class "Default")
      (node (ref "R7") (pin "2") (pinfunction "2_2") (pintype "passive"))
      (node (ref "U1") (pin "4") (pinfunction "EXCB_4") (pintype "passive"))
    )
    (net (code "72") (name "Net-(U2-EXCA)") (class "Default")
      (node (ref "R4") (pin "1") (pinfunction "1_1") (pintype "passive"))
      (node (ref "U2") (pin "3") (pinfunction "EXCA_3") (pintype "passive"))
    )
    (net (code "73") (name "Net-(U2-EXCB)") (class "Default")
      (node (ref "R8") (pin "2") (pinfunction "2_2") (pintype "passive"))
      (node (ref "U2") (pin "4") (pinfunction "EXCB_4") (pintype "passive"))
    )
    (net (code "74") (name "Net-(U3-+IN)") (class "Default")
      (node (ref "R1") (pin "2") (pinfunction "2_2") (pintype "passive"))
      (node (ref "R7") (pin "1") (pinfunction "1_1") (pintype "passive"))
      (node (ref "U3") (pin "3") (pinfunction "+IN_3") (pintype "passive"))
    )
    (net (code "75") (name "Net-(U4-+IN)") (class "Default")
      (node (ref "R4") (pin "2") (pinfunction "2_2") (pintype "passive"))
      (node (ref "R8") (pin "1") (pinfunction "1_1") (pintype "passive"))
      (node (ref "U4") (pin "3") (pinfunction "+IN_3") (pintype "passive"))
    )
    (net (code "76") (name "Net-(U9-EXCA)") (class "Default")
      (node (ref "R13") (pin "1") (pinfunction "1_1") (pintype "passive"))
      (node (ref "U9") (pin "3") (pinfunction "EXCA_3") (pintype "passive"))
    )
    (net (code "77") (name "Net-(U9-EXCB)") (class "Default")
      (node (ref "R19") (pin "2") (pinfunction "2_2") (pintype "passive"))
      (node (ref "U9") (pin "4") (pinfunction "EXCB_4") (pintype "passive"))
    )
    (net (code "78") (name "Net-(U10-+IN)") (class "Default")
      (node (ref "R13") (pin "2") (pinfunction "2_2") (pintype "passive"))
      (node (ref "R19") (pin "1") (pinfunction "1_1") (pintype "passive"))
      (node (ref "U10") (pin "3") (pinfunction "+IN_3") (pintype "passive"))
    )
    (net (code "79") (name "Net-(U11-EXCA)") (class "Default")
      (node (ref "R16") (pin "1") (pinfunction "1_1") (pintype "passive"))
      (node (ref "U11") (pin "3") (pinfunction "EXCA_3") (pintype "passive"))
    )
    (net (code "80") (name "Net-(U11-EXCB)") (class "Default")
      (node (ref "R20") (pin "2") (pinfunction "2_2") (pintype "passive"))
      (node (ref "U11") (pin "4") (pinfunction "EXCB_4") (pintype "passive"))
    )
    (net (code "81") (name "Net-(U12-+IN)") (class "Default")
      (node (ref "R16") (pin "2") (pinfunction "2_2") (pintype "passive"))
      (node (ref "R20") (pin "1") (pinfunction "1_1") (pintype "passive"))
      (node (ref "U12") (pin "3") (pinfunction "+IN_3") (pintype "passive"))
    )
    (net (code "82") (name "VDD_3V3") (class "Default")
      (node (ref "C10") (pin "2") (pinfunction "2_2") (pintype "passive"))
      (node (ref "C11") (pin "1") (pinfunction "1_1") (pintype "passive"))
      (node (ref "C12") (pin "1") (pinfunction "1_1") (pintype "passive"))
      (node (ref "C13") (pin "2") (pinfunction "2_2") (pintype "passive"))
      (node (ref "C14") (pin "2") (pinfunction "2_2") (pintype "passive"))
      (node (ref "C21") (pin "1") (pinfunction "1_1") (pintype "passive"))
      (node (ref "C22") (pin "1") (pinfunction "1_1") (pintype "passive"))
      (node (ref "C23") (pin "1") (pinfunction "1_1") (pintype "passive"))
      (node (ref "C24") (pin "2") (pinfunction "2_2") (pintype "passive"))
      (node (ref "C25") (pin "2") (pinfunction "2_2") (pintype "passive"))
      (node (ref "C26") (pin "2") (pinfunction "2_2") (pintype "passive"))
      (node (ref "C27") (pin "1") (pinfunction "1_1") (pintype "passive"))
      (node (ref "C28") (pin "2") (pinfunction "2_2") (pintype "passive"))
      (node (ref "C7") (pin "1") (pinfunction "1_1") (pintype "passive"))
      (node (ref "C8") (pin "1") (pinfunction "1_1") (pintype "passive"))
      (node (ref "C9") (pin "2") (pinfunction "2_2") (pintype "passive"))
      (node (ref "P3") (pin "1") (pinfunction "1_1") (pintype "passive"))
      (node (ref "P3") (pin "2") (pinfunction "2_2") (pintype "passive"))
      (node (ref "U13") (pin "16") (pinfunction "VDD_16") (pintype "passive"))
      (node (ref "U14") (pin "16") (pinfunction "VDD_16") (pintype "passive"))
      (node (ref "U15") (pin "16") (pinfunction "VDD_16") (pintype "passive"))
      (node (ref "U16") (pin "16") (pinfunction "VDD_16") (pintype "passive"))
      (node (ref "U5") (pin "16") (pinfunction "VDD_16") (pintype "passive"))
      (node (ref "U6") (pin "16") (pinfunction "VDD_16") (pintype "passive"))
      (node (ref "U7") (pin "16") (pinfunction "VDD_16") (pintype "passive"))
      (node (ref "U8") (pin "16") (pinfunction "VDD_16") (pintype "passive"))
    )
    (net (code "83") (name "VDD_5V") (class "Default")
      (node (ref "C1") (pin "1") (pinfunction "1_1") (pintype "passive"))
      (node (ref "C15") (pin "1") (pinfunction "1_1") (pintype "passive"))
      (node (ref "C16") (pin "2") (pinfunction "2_2") (pintype "passive"))
      (node (ref "C17") (pin "1") (pinfunction "1_1") (pintype "passive"))
      (node (ref "C18") (pin "2") (pinfunction "2_2") (pintype "passive"))
      (node (ref "C19") (pin "2") (pinfunction "2_2") (pintype "passive"))
      (node (ref "C2") (pin "2") (pinfunction "2_2") (pintype "passive"))
      (node (ref "C20") (pin "2") (pinfunction "2_2") (pintype "passive"))
      (node (ref "C3") (pin "1") (pinfunction "1_1") (pintype "passive"))
      (node (ref "C4") (pin "2") (pinfunction "2_2") (pintype "passive"))
      (node (ref "C5") (pin "2") (pinfunction "2_2") (pintype "passive"))
      (node (ref "C6") (pin "2") (pinfunction "2_2") (pintype "passive"))
      (node (ref "P1") (pin "1") (pinfunction "1_1") (pintype "passive"))
      (node (ref "P1") (pin "2") (pinfunction "2_2") (pintype "passive"))
      (node (ref "R14") (pin "2") (pinfunction "2_2") (pintype "passive"))
      (node (ref "R15") (pin "2") (pinfunction "2_2") (pintype "passive"))
      (node (ref "R17") (pin "2") (pinfunction "2_2") (pintype "passive"))
      (node (ref "R18") (pin "2") (pinfunction "2_2") (pintype "passive"))
      (node (ref "R2") (pin "2") (pinfunction "2_2") (pintype "passive"))
      (node (ref "R3") (pin "2") (pinfunction "2_2") (pintype "passive"))
      (node (ref "R5") (pin "2") (pinfunction "2_2") (pintype "passive"))
      (node (ref "R6") (pin "2") (pinfunction "2_2") (pintype "passive"))
      (node (ref "U1") (pin "14") (pinfunction "VDD_14") (pintype "passive"))
      (node (ref "U10") (pin "5") (pinfunction "V+_5") (pintype "passive"))
      (node (ref "U11") (pin "14") (pinfunction "VDD_14") (pintype "passive"))
      (node (ref "U12") (pin "5") (pinfunction "V+_5") (pintype "passive"))
      (node (ref "U2") (pin "14") (pinfunction "VDD_14") (pintype "passive"))
      (node (ref "U3") (pin "5") (pinfunction "V+_5") (pintype "passive"))
      (node (ref "U4") (pin "5") (pinfunction "V+_5") (pintype "passive"))
      (node (ref "U9") (pin "14") (pinfunction "VDD_14") (pintype "passive"))
    )
    (net (code "84") (name "unconnected-(J1-Pad9)") (class "Default")
      (node (ref "J1") (pin "9") (pinfunction "9_9") (pintype "passive+no_connect"))
    )
    (net (code "85") (name "unconnected-(J1-Pad10)") (class "Default")
      (node (ref "J1") (pin "10") (pinfunction "10_10") (pintype "passive+no_connect"))
    )
    (net (code "86") (name "unconnected-(J2-Pad9)") (class "Default")
      (node (ref "J2") (pin "9") (pinfunction "9_9") (pintype "passive+no_connect"))
    )
    (net (code "87") (name "unconnected-(J2-Pad10)") (class "Default")
      (node (ref "J2") (pin "10") (pinfunction "10_10") (pintype "passive+no_connect"))
    )
    (net (code "88") (name "unconnected-(U1-CIN1(-)-Pad7)") (class "Default")
      (node (ref "U1") (pin "7") (pinfunction "CIN1(-)_7") (pintype "passive+no_connect"))
    )
    (net (code "89") (name "unconnected-(U1-CIN2(+)-Pad9)") (class "Default")
      (node (ref "U1") (pin "9") (pinfunction "CIN2(+)_9") (pintype "passive+no_connect"))
    )
    (net (code "90") (name "unconnected-(U1-CIN2(-)-Pad10)") (class "Default")
      (node (ref "U1") (pin "10") (pinfunction "CIN2(-)_10") (pintype "passive+no_connect"))
    )
    (net (code "91") (name "unconnected-(U1-NC-Pad15)") (class "Default")
      (node (ref "U1") (pin "15") (pinfunction "NC_15") (pintype "passive+no_connect"))
    )
    (net (code "92") (name "unconnected-(U1-REFIN(+)-Pad5)") (class "Default")
      (node (ref "U1") (pin "5") (pinfunction "REFIN(+)_5") (pintype "passive+no_connect"))
    )
    (net (code "93") (name "unconnected-(U1-REFIN(-)-Pad6)") (class "Default")
      (node (ref "U1") (pin "6") (pinfunction "REFIN(-)_6") (pintype "passive+no_connect"))
    )
    (net (code "94") (name "unconnected-(U1-VIN(+)-Pad11)") (class "Default")
      (node (ref "U1") (pin "11") (pinfunction "VIN(+)_11") (pintype "passive+no_connect"))
    )
    (net (code "95") (name "unconnected-(U1-VIN(-)-Pad12)") (class "Default")
      (node (ref "U1") (pin "12") (pinfunction "VIN(-)_12") (pintype "passive+no_connect"))
    )
    (net (code "96") (name "unconnected-(U2-CIN1(-)-Pad7)") (class "Default")
      (node (ref "U2") (pin "7") (pinfunction "CIN1(-)_7") (pintype "passive+no_connect"))
    )
    (net (code "97") (name "unconnected-(U2-CIN2(+)-Pad9)") (class "Default")
      (node (ref "U2") (pin "9") (pinfunction "CIN2(+)_9") (pintype "passive+no_connect"))
    )
    (net (code "98") (name "unconnected-(U2-CIN2(-)-Pad10)") (class "Default")
      (node (ref "U2") (pin "10") (pinfunction "CIN2(-)_10") (pintype "passive+no_connect"))
    )
    (net (code "99") (name "unconnected-(U2-NC-Pad15)") (class "Default")
      (node (ref "U2") (pin "15") (pinfunction "NC_15") (pintype "passive+no_connect"))
    )
    (net (code "100") (name "unconnected-(U2-REFIN(+)-Pad5)") (class "Default")
      (node (ref "U2") (pin "5") (pinfunction "REFIN(+)_5") (pintype "passive+no_connect"))
    )
    (net (code "101") (name "unconnected-(U2-REFIN(-)-Pad6)") (class "Default")
      (node (ref "U2") (pin "6") (pinfunction "REFIN(-)_6") (pintype "passive+no_connect"))
    )
    (net (code "102") (name "unconnected-(U2-VIN(+)-Pad11)") (class "Default")
      (node (ref "U2") (pin "11") (pinfunction "VIN(+)_11") (pintype "passive+no_connect"))
    )
    (net (code "103") (name "unconnected-(U2-VIN(-)-Pad12)") (class "Default")
      (node (ref "U2") (pin "12") (pinfunction "VIN(-)_12") (pintype "passive+no_connect"))
    )
    (net (code "104") (name "unconnected-(U5-CH4-Pad1)") (class "Default")
      (node (ref "U5") (pin "1") (pinfunction "CH4_1") (pintype "passive+no_connect"))
    )
    (net (code "105") (name "unconnected-(U5-CH5-Pad5)") (class "Default")
      (node (ref "U5") (pin "5") (pinfunction "CH5_5") (pintype "passive+no_connect"))
    )
    (net (code "106") (name "unconnected-(U5-CH6-Pad2)") (class "Default")
      (node (ref "U5") (pin "2") (pinfunction "CH6_2") (pintype "passive+no_connect"))
    )
    (net (code "107") (name "unconnected-(U5-CH7-Pad4)") (class "Default")
      (node (ref "U5") (pin "4") (pinfunction "CH7_4") (pintype "passive+no_connect"))
    )
    (net (code "108") (name "unconnected-(U6-CH4-Pad1)") (class "Default")
      (node (ref "U6") (pin "1") (pinfunction "CH4_1") (pintype "passive+no_connect"))
    )
    (net (code "109") (name "unconnected-(U6-CH5-Pad5)") (class "Default")
      (node (ref "U6") (pin "5") (pinfunction "CH5_5") (pintype "passive+no_connect"))
    )
    (net (code "110") (name "unconnected-(U6-CH6-Pad2)") (class "Default")
      (node (ref "U6") (pin "2") (pinfunction "CH6_2") (pintype "passive+no_connect"))
    )
    (net (code "111") (name "unconnected-(U6-CH7-Pad4)") (class "Default")
      (node (ref "U6") (pin "4") (pinfunction "CH7_4") (pintype "passive+no_connect"))
    )
    (net (code "112") (name "unconnected-(U7-CH4-Pad1)") (class "Default")
      (node (ref "U7") (pin "1") (pinfunction "CH4_1") (pintype "passive+no_connect"))
    )
    (net (code "113") (name "unconnected-(U7-CH5-Pad5)") (class "Default")
      (node (ref "U7") (pin "5") (pinfunction "CH5_5") (pintype "passive+no_connect"))
    )
    (net (code "114") (name "unconnected-(U7-CH6-Pad2)") (class "Default")
      (node (ref "U7") (pin "2") (pinfunction "CH6_2") (pintype "passive+no_connect"))
    )
    (net (code "115") (name "unconnected-(U7-CH7-Pad4)") (class "Default")
      (node (ref "U7") (pin "4") (pinfunction "CH7_4") (pintype "passive+no_connect"))
    )
    (net (code "116") (name "unconnected-(U8-CH4-Pad1)") (class "Default")
      (node (ref "U8") (pin "1") (pinfunction "CH4_1") (pintype "passive+no_connect"))
    )
    (net (code "117") (name "unconnected-(U8-CH5-Pad5)") (class "Default")
      (node (ref "U8") (pin "5") (pinfunction "CH5_5") (pintype "passive+no_connect"))
    )
    (net (code "118") (name "unconnected-(U8-CH6-Pad2)") (class "Default")
      (node (ref "U8") (pin "2") (pinfunction "CH6_2") (pintype "passive+no_connect"))
    )
    (net (code "119") (name "unconnected-(U8-CH7-Pad4)") (class "Default")
      (node (ref "U8") (pin "4") (pinfunction "CH7_4") (pintype "passive+no_connect"))
    )
    (net (code "120") (name "unconnected-(U9-CIN1(-)-Pad7)") (class "Default")
      (node (ref "U9") (pin "7") (pinfunction "CIN1(-)_7") (pintype "passive+no_connect"))
    )
    (net (code "121") (name "unconnected-(U9-CIN2(+)-Pad9)") (class "Default")
      (node (ref "U9") (pin "9") (pinfunction "CIN2(+)_9") (pintype "passive+no_connect"))
    )
    (net (code "122") (name "unconnected-(U9-CIN2(-)-Pad10)") (class "Default")
      (node (ref "U9") (pin "10") (pinfunction "CIN2(-)_10") (pintype "passive+no_connect"))
    )
    (net (code "123") (name "unconnected-(U9-NC-Pad15)") (class "Default")
      (node (ref "U9") (pin "15") (pinfunction "NC_15") (pintype "passive+no_connect"))
    )
    (net (code "124") (name "unconnected-(U9-REFIN(+)-Pad5)") (class "Default")
      (node (ref "U9") (pin "5") (pinfunction "REFIN(+)_5") (pintype "passive+no_connect"))
    )
    (net (code "125") (name "unconnected-(U9-REFIN(-)-Pad6)") (class "Default")
      (node (ref "U9") (pin "6") (pinfunction "REFIN(-)_6") (pintype "passive+no_connect"))
    )
    (net (code "126") (name "unconnected-(U9-VIN(+)-Pad11)") (class "Default")
      (node (ref "U9") (pin "11") (pinfunction "VIN(+)_11") (pintype "passive+no_connect"))
    )
    (net (code "127") (name "unconnected-(U9-VIN(-)-Pad12)") (class "Default")
      (node (ref "U9") (pin "12") (pinfunction "VIN(-)_12") (pintype "passive+no_connect"))
    )
    (net (code "128") (name "unconnected-(U11-CIN1(-)-Pad7)") (class "Default")
      (node (ref "U11") (pin "7") (pinfunction "CIN1(-)_7") (pintype "passive+no_connect"))
    )
    (net (code "129") (name "unconnected-(U11-CIN2(+)-Pad9)") (class "Default")
      (node (ref "U11") (pin "9") (pinfunction "CIN2(+)_9") (pintype "passive+no_connect"))
    )
    (net (code "130") (name "unconnected-(U11-CIN2(-)-Pad10)") (class "Default")
      (node (ref "U11") (pin "10") (pinfunction "CIN2(-)_10") (pintype "passive+no_connect"))
    )
    (net (code "131") (name "unconnected-(U11-NC-Pad15)") (class "Default")
      (node (ref "U11") (pin "15") (pinfunction "NC_15") (pintype "passive+no_connect"))
    )
    (net (code "132") (name "unconnected-(U11-REFIN(+)-Pad5)") (class "Default")
      (node (ref "U11") (pin "5") (pinfunction "REFIN(+)_5") (pintype "passive+no_connect"))
    )
    (net (code "133") (name "unconnected-(U11-REFIN(-)-Pad6)") (class "Default")
      (node (ref "U11") (pin "6") (pinfunction "REFIN(-)_6") (pintype "passive+no_connect"))
    )
    (net (code "134") (name "unconnected-(U11-VIN(+)-Pad11)") (class "Default")
      (node (ref "U11") (pin "11") (pinfunction "VIN(+)_11") (pintype "passive+no_connect"))
    )
    (net (code "135") (name "unconnected-(U11-VIN(-)-Pad12)") (class "Default")
      (node (ref "U11") (pin "12") (pinfunction "VIN(-)_12") (pintype "passive+no_connect"))
    )
    (net (code "136") (name "unconnected-(U13-CH4-Pad1)") (class "Default")
      (node (ref "U13") (pin "1") (pinfunction "CH4_1") (pintype "passive+no_connect"))
    )
    (net (code "137") (name "unconnected-(U13-CH5-Pad5)") (class "Default")
      (node (ref "U13") (pin "5") (pinfunction "CH5_5") (pintype "passive+no_connect"))
    )
    (net (code "138") (name "unconnected-(U13-CH6-Pad2)") (class "Default")
      (node (ref "U13") (pin "2") (pinfunction "CH6_2") (pintype "passive+no_connect"))
    )
    (net (code "139") (name "unconnected-(U13-CH7-Pad4)") (class "Default")
      (node (ref "U13") (pin "4") (pinfunction "CH7_4") (pintype "passive+no_connect"))
    )
    (net (code "140") (name "unconnected-(U14-CH4-Pad1)") (class "Default")
      (node (ref "U14") (pin "1") (pinfunction "CH4_1") (pintype "passive+no_connect"))
    )
    (net (code "141") (name "unconnected-(U14-CH5-Pad5)") (class "Default")
      (node (ref "U14") (pin "5") (pinfunction "CH5_5") (pintype "passive+no_connect"))
    )
    (net (code "142") (name "unconnected-(U14-CH6-Pad2)") (class "Default")
      (node (ref "U14") (pin "2") (pinfunction "CH6_2") (pintype "passive+no_connect"))
    )
    (net (code "143") (name "unconnected-(U14-CH7-Pad4)") (class "Default")
      (node (ref "U14") (pin "4") (pinfunction "CH7_4") (pintype "passive+no_connect"))
    )
    (net (code "144") (name "unconnected-(U15-CH4-Pad1)") (class "Default")
      (node (ref "U15") (pin "1") (pinfunction "CH4_1") (pintype "passive+no_connect"))
    )
    (net (code "145") (name "unconnected-(U15-CH5-Pad5)") (class "Default")
      (node (ref "U15") (pin "5") (pinfunction "CH5_5") (pintype "passive+no_connect"))
    )
    (net (code "146") (name "unconnected-(U15-CH6-Pad2)") (class "Default")
      (node (ref "U15") (pin "2") (pinfunction "CH6_2") (pintype "passive+no_connect"))
    )
    (net (code "147") (name "unconnected-(U15-CH7-Pad4)") (class "Default")
      (node (ref "U15") (pin "4") (pinfunction "CH7_4") (pintype "passive+no_connect"))
    )
    (net (code "148") (name "unconnected-(U16-CH4-Pad1)") (class "Default")
      (node (ref "U16") (pin "1") (pinfunction "CH4_1") (pintype "passive+no_connect"))
    )
    (net (code "149") (name "unconnected-(U16-CH5-Pad5)") (class "Default")
      (node (ref "U16") (pin "5") (pinfunction "CH5_5") (pintype "passive+no_connect"))
    )
    (net (code "150") (name "unconnected-(U16-CH6-Pad2)") (class "Default")
      (node (ref "U16") (pin "2") (pinfunction "CH6_2") (pintype "passive+no_connect"))
    )
    (net (code "151") (name "unconnected-(U16-CH7-Pad4)") (class "Default")
      (node (ref "U16") (pin "4") (pinfunction "CH7_4") (pintype "passive+no_connect"))
    )
  )
)
